# ADC.net
KiCad netlist of a schematic drawn in Altium Designer
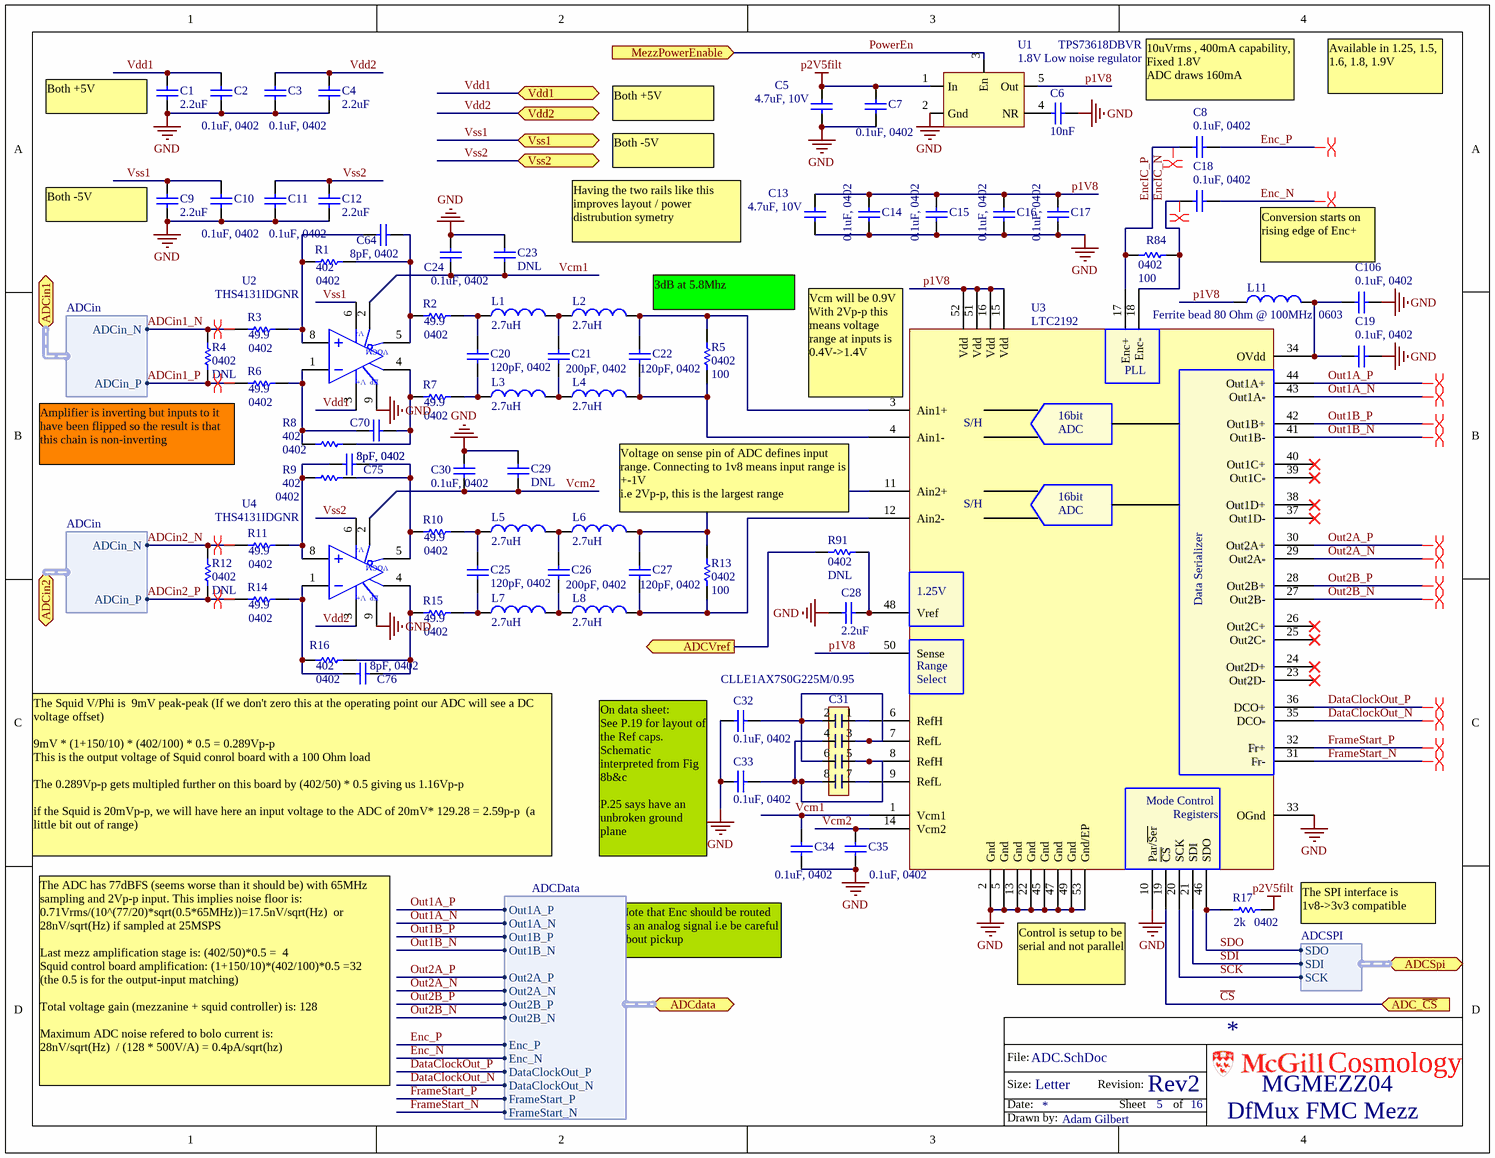
[diagram p0: ADC.SchDoc]

(export (version "E")
  (design (tool "Eeschema 10.0.6"))
  (components
    (comp (ref "C1")
      (value "2.2uF")
      (footprint "0603")
      (description "Capacitor, Ceramic, 0603")
      (fields (field (name "MANUFACTURER") "TDK Corporation"))
      (libsource (lib "MGMEZZ04") (part "CAP 0603"))
    )
    (comp (ref "C2")
      (value "0.1uF, 0402")
      (footprint "0402")
      (description "Capacitor, Ceramic, 0402")
      (fields (field (name "MANUFACTURER") "TDK Corporation"))
      (libsource (lib "MGMEZZ04") (part "CAP 0603"))
    )
    (comp (ref "C3")
      (value "0.1uF, 0402")
      (footprint "0402")
      (description "Capacitor, Ceramic, 0402")
      (fields (field (name "MANUFACTURER") "TDK Corporation"))
      (libsource (lib "MGMEZZ04") (part "CAP 0603"))
    )
    (comp (ref "C4")
      (value "2.2uF")
      (footprint "0603")
      (description "Capacitor, Ceramic, 0603")
      (fields (field (name "MANUFACTURER") "TDK Corporation"))
      (libsource (lib "MGMEZZ04") (part "CAP 0603"))
    )
    (comp (ref "C5")
      (value "4.7uF, 10V")
      (footprint "0805")
      (description "Capacitor, Ceramic, 0805")
      (fields (field (name "MANUFACTURER") "Taiyo Yuden"))
      (libsource (lib "MGMEZZ04") (part "CAP 0805"))
    )
    (comp (ref "C6")
      (value "10nF")
      (footprint "0603")
      (description "Capacitor, Ceramic, 0603")
      (fields (field (name "MANUFACTURER") "Generic"))
      (libsource (lib "MGMEZZ04") (part "CAP 0603"))
    )
    (comp (ref "C7")
      (value "0.1uF, 0402")
      (footprint "0402")
      (description "Capacitor, Ceramic, 0402")
      (fields (field (name "MANUFACTURER") "TDK Corporation"))
      (libsource (lib "MGMEZZ04") (part "CAP 0603"))
    )
    (comp (ref "C8")
      (value "0.1uF, 0402")
      (footprint "0402")
      (description "Capacitor, Ceramic, 0402")
      (fields (field (name "MANUFACTURER") "TDK Corporation"))
      (libsource (lib "MGMEZZ04") (part "CAP 0603"))
    )
    (comp (ref "C9")
      (value "2.2uF")
      (footprint "0603")
      (description "Capacitor, Ceramic, 0603")
      (fields (field (name "MANUFACTURER") "TDK Corporation"))
      (libsource (lib "MGMEZZ04") (part "CAP 0603"))
    )
    (comp (ref "C10")
      (value "0.1uF, 0402")
      (footprint "0402")
      (description "Capacitor, Ceramic, 0402")
      (fields (field (name "MANUFACTURER") "TDK Corporation"))
      (libsource (lib "MGMEZZ04") (part "CAP 0603"))
    )
    (comp (ref "C11")
      (value "0.1uF, 0402")
      (footprint "0402")
      (description "Capacitor, Ceramic, 0402")
      (fields (field (name "MANUFACTURER") "TDK Corporation"))
      (libsource (lib "MGMEZZ04") (part "CAP 0603"))
    )
    (comp (ref "C12")
      (value "2.2uF")
      (footprint "0603")
      (description "Capacitor, Ceramic, 0603")
      (fields (field (name "MANUFACTURER") "TDK Corporation"))
      (libsource (lib "MGMEZZ04") (part "CAP 0603"))
    )
    (comp (ref "C13")
      (value "4.7uF, 10V")
      (footprint "0805")
      (description "Capacitor, Ceramic, 0805")
      (fields (field (name "MANUFACTURER") "Taiyo Yuden"))
      (libsource (lib "MGMEZZ04") (part "CAP 0805"))
    )
    (comp (ref "C14")
      (value "0.1uF, 0402")
      (footprint "0402")
      (description "Capacitor, Ceramic, 0402")
      (fields (field (name "MANUFACTURER") "TDK Corporation"))
      (libsource (lib "MGMEZZ04") (part "CAP 0603"))
    )
    (comp (ref "C15")
      (value "0.1uF, 0402")
      (footprint "0402")
      (description "Capacitor, Ceramic, 0402")
      (fields (field (name "MANUFACTURER") "TDK Corporation"))
      (libsource (lib "MGMEZZ04") (part "CAP 0603"))
    )
    (comp (ref "C16")
      (value "0.1uF, 0402")
      (footprint "0402")
      (description "Capacitor, Ceramic, 0402")
      (fields (field (name "MANUFACTURER") "TDK Corporation"))
      (libsource (lib "MGMEZZ04") (part "CAP 0603"))
    )
    (comp (ref "C17")
      (value "0.1uF, 0402")
      (footprint "0402")
      (description "Capacitor, Ceramic, 0402")
      (fields (field (name "MANUFACTURER") "TDK Corporation"))
      (libsource (lib "MGMEZZ04") (part "CAP 0603"))
    )
    (comp (ref "C18")
      (value "0.1uF, 0402")
      (footprint "0402")
      (description "Capacitor, Ceramic, 0402")
      (fields (field (name "MANUFACTURER") "TDK Corporation"))
      (libsource (lib "MGMEZZ04") (part "CAP 0603"))
    )
    (comp (ref "C19")
      (value "0.1uF, 0402")
      (footprint "0402")
      (description "Capacitor, Ceramic, 0402")
      (fields (field (name "MANUFACTURER") "TDK Corporation"))
      (libsource (lib "MGMEZZ04") (part "CAP 0603"))
    )
    (comp (ref "C20")
      (value "120pF, 0402")
      (footprint "0402")
      (description "Capacitor, Ceramic, 0402")
      (fields (field (name "MANUFACTURER") "Generic"))
      (libsource (lib "MGMEZZ04") (part "CAP 0402"))
    )
    (comp (ref "C21")
      (value "200pF, 0402")
      (footprint "0402")
      (description "Capacitor, Ceramic, 0402")
      (fields (field (name "MANUFACTURER") "Generic"))
      (libsource (lib "MGMEZZ04") (part "CAP 0402"))
    )
    (comp (ref "C22")
      (value "120pF, 0402")
      (footprint "0402")
      (description "Capacitor, Ceramic, 0402")
      (fields (field (name "MANUFACTURER") "Generic"))
      (libsource (lib "MGMEZZ04") (part "CAP 0402"))
    )
    (comp (ref "C23")
      (value "DNL")
      (footprint "0603")
      (description "Capacitor, Ceramic, 0603")
      (fields (field (name "MANUFACTURER") "TDK Corporation"))
      (libsource (lib "MGMEZZ04") (part "CAP 0603"))
    )
    (comp (ref "C24")
      (value "0.1uF, 0402")
      (footprint "0402")
      (description "Capacitor, Ceramic, 0402")
      (fields (field (name "MANUFACTURER") "TDK Corporation"))
      (libsource (lib "MGMEZZ04") (part "CAP 0603"))
    )
    (comp (ref "C25")
      (value "120pF, 0402")
      (footprint "0402")
      (description "Capacitor, Ceramic, 0402")
      (fields (field (name "MANUFACTURER") "Generic"))
      (libsource (lib "MGMEZZ04") (part "CAP 0402"))
    )
    (comp (ref "C26")
      (value "200pF, 0402")
      (footprint "0402")
      (description "Capacitor, Ceramic, 0402")
      (fields (field (name "MANUFACTURER") "Generic"))
      (libsource (lib "MGMEZZ04") (part "CAP 0402"))
    )
    (comp (ref "C27")
      (value "120pF, 0402")
      (footprint "0402")
      (description "Capacitor, Ceramic, 0402")
      (fields (field (name "MANUFACTURER") "Generic"))
      (libsource (lib "MGMEZZ04") (part "CAP 0402"))
    )
    (comp (ref "C28")
      (value "2.2uF")
      (footprint "0603")
      (description "Capacitor, Ceramic, 0603")
      (fields (field (name "MANUFACTURER") "TDK Corporation"))
      (libsource (lib "MGMEZZ04") (part "CAP 0603"))
    )
    (comp (ref "C29")
      (value "DNL")
      (footprint "0603")
      (description "Capacitor, Ceramic, 0603")
      (fields (field (name "MANUFACTURER") "TDK Corporation"))
      (libsource (lib "MGMEZZ04") (part "CAP 0603"))
    )
    (comp (ref "C30")
      (value "0.1uF, 0402")
      (footprint "0402")
      (description "Capacitor, Ceramic, 0402")
      (fields (field (name "MANUFACTURER") "TDK Corporation"))
      (libsource (lib "MGMEZZ04") (part "CAP 0603"))
    )
    (comp (ref "C31")
      (value "CLLE1AX7S0G225M/0.95")
      (footprint "CLLE1")
      (description "2.2uFx4 4V 0805 Cap Array")
      (fields (field (name "MANUFACTURER") "TDK Corporation"))
      (libsource (lib "MGMEZZ04") (part "CapArray0805"))
    )
    (comp (ref "C32")
      (value "0.1uF, 0402")
      (footprint "0402")
      (description "Capacitor, Ceramic, 0402")
      (fields (field (name "MANUFACTURER") "TDK Corporation"))
      (libsource (lib "MGMEZZ04") (part "CAP 0603"))
    )
    (comp (ref "C33")
      (value "0.1uF, 0402")
      (footprint "0402")
      (description "Capacitor, Ceramic, 0402")
      (fields (field (name "MANUFACTURER") "TDK Corporation"))
      (libsource (lib "MGMEZZ04") (part "CAP 0603"))
    )
    (comp (ref "C34")
      (value "0.1uF, 0402")
      (footprint "0402")
      (description "Capacitor, Ceramic, 0402")
      (fields (field (name "MANUFACTURER") "TDK Corporation"))
      (libsource (lib "MGMEZZ04") (part "CAP 0603"))
    )
    (comp (ref "C35")
      (value "0.1uF, 0402")
      (footprint "0402")
      (description "Capacitor, Ceramic, 0402")
      (fields (field (name "MANUFACTURER") "TDK Corporation"))
      (libsource (lib "MGMEZZ04") (part "CAP 0603"))
    )
    (comp (ref "C64")
      (value "8pF, 0402")
      (footprint "0402")
      (description "Capacitor, Ceramic, 0402")
      (fields (field (name "MANUFACTURER") "Generic"))
      (libsource (lib "MGMEZZ04") (part "CAP 0402"))
    )
    (comp (ref "C70")
      (value "8pF, 0402")
      (footprint "0402")
      (description "Capacitor, Ceramic, 0402")
      (fields (field (name "MANUFACTURER") "Generic"))
      (libsource (lib "MGMEZZ04") (part "CAP 0402"))
    )
    (comp (ref "C75")
      (value "8pF, 0402")
      (footprint "0402")
      (description "Capacitor, Ceramic, 0402")
      (fields (field (name "MANUFACTURER") "Generic"))
      (libsource (lib "MGMEZZ04") (part "CAP 0402"))
    )
    (comp (ref "C76")
      (value "8pF, 0402")
      (footprint "0402")
      (description "Capacitor, Ceramic, 0402")
      (fields (field (name "MANUFACTURER") "Generic"))
      (libsource (lib "MGMEZZ04") (part "CAP 0402"))
    )
    (comp (ref "C106")
      (value "0.1uF, 0402")
      (footprint "0402")
      (description "Capacitor, Ceramic, 0402")
      (fields (field (name "MANUFACTURER") "TDK Corporation"))
      (libsource (lib "MGMEZZ04") (part "CAP 0603"))
    )
    (comp (ref "L1")
      (value "2.7uH")
      (footprint "0603")
      (description "Inductor 0603")
      (fields (field (name "MANUFACTURER") "TDK Corporation"))
      (libsource (lib "MGMEZZ04") (part "IND 0603"))
    )
    (comp (ref "L2")
      (value "2.7uH")
      (footprint "0603")
      (description "Inductor 0603")
      (fields (field (name "MANUFACTURER") "TDK Corporation"))
      (libsource (lib "MGMEZZ04") (part "IND 0603"))
    )
    (comp (ref "L3")
      (value "2.7uH")
      (footprint "0603")
      (description "Inductor 0603")
      (fields (field (name "MANUFACTURER") "TDK Corporation"))
      (libsource (lib "MGMEZZ04") (part "IND 0603"))
    )
    (comp (ref "L4")
      (value "2.7uH")
      (footprint "0603")
      (description "Inductor 0603")
      (fields (field (name "MANUFACTURER") "TDK Corporation"))
      (libsource (lib "MGMEZZ04") (part "IND 0603"))
    )
    (comp (ref "L5")
      (value "2.7uH")
      (footprint "0603")
      (description "Inductor 0603")
      (fields (field (name "MANUFACTURER") "TDK Corporation"))
      (libsource (lib "MGMEZZ04") (part "IND 0603"))
    )
    (comp (ref "L6")
      (value "2.7uH")
      (footprint "0603")
      (description "Inductor 0603")
      (fields (field (name "MANUFACTURER") "TDK Corporation"))
      (libsource (lib "MGMEZZ04") (part "IND 0603"))
    )
    (comp (ref "L7")
      (value "2.7uH")
      (footprint "0603")
      (description "Inductor 0603")
      (fields (field (name "MANUFACTURER") "TDK Corporation"))
      (libsource (lib "MGMEZZ04") (part "IND 0603"))
    )
    (comp (ref "L8")
      (value "2.7uH")
      (footprint "0603")
      (description "Inductor 0603")
      (fields (field (name "MANUFACTURER") "TDK Corporation"))
      (libsource (lib "MGMEZZ04") (part "IND 0603"))
    )
    (comp (ref "L11")
      (value "Ferrite bead 80 Ohm @ 100MHz  0603")
      (footprint "0603")
      (description "Inductor 0603")
      (fields (field (name "MANUFACTURER") "Abracon Corporation"))
      (libsource (lib "MGMEZZ04") (part "IND 0603"))
    )
    (comp (ref "R1")
      (value "402")
      (footprint "0402")
      (description "Resistor")
      (fields (field (name "MANUFACTURER") "Generic"))
      (libsource (lib "MGMEZZ04") (part "RES 0402"))
    )
    (comp (ref "R2")
      (value "49.9")
      (footprint "0402")
      (description "Resistor")
      (fields (field (name "MANUFACTURER") "Generic"))
      (libsource (lib "MGMEZZ04") (part "RES 0402"))
    )
    (comp (ref "R3")
      (value "49.9")
      (footprint "0402")
      (description "Resistor")
      (fields (field (name "MANUFACTURER") "Generic"))
      (libsource (lib "MGMEZZ04") (part "RES 0402"))
    )
    (comp (ref "R4")
      (value "DNL")
      (footprint "0402")
      (description "Resistor")
      (fields (field (name "MANUFACTURER") "Generic"))
      (libsource (lib "MGMEZZ04") (part "RES 0402"))
    )
    (comp (ref "R5")
      (value "100")
      (footprint "0402")
      (description "Resistor")
      (fields (field (name "MANUFACTURER") "Generic"))
      (libsource (lib "MGMEZZ04") (part "RES 0402"))
    )
    (comp (ref "R6")
      (value "49.9")
      (footprint "0402")
      (description "Resistor")
      (fields (field (name "MANUFACTURER") "Generic"))
      (libsource (lib "MGMEZZ04") (part "RES 0402"))
    )
    (comp (ref "R7")
      (value "49.9")
      (footprint "0402")
      (description "Resistor")
      (fields (field (name "MANUFACTURER") "Generic"))
      (libsource (lib "MGMEZZ04") (part "RES 0402"))
    )
    (comp (ref "R8")
      (value "402")
      (footprint "0402")
      (description "Resistor")
      (fields (field (name "MANUFACTURER") "Generic"))
      (libsource (lib "MGMEZZ04") (part "RES 0402"))
    )
    (comp (ref "R9")
      (value "402")
      (footprint "0402")
      (description "Resistor")
      (fields (field (name "MANUFACTURER") "Generic"))
      (libsource (lib "MGMEZZ04") (part "RES 0402"))
    )
    (comp (ref "R10")
      (value "49.9")
      (footprint "0402")
      (description "Resistor")
      (fields (field (name "MANUFACTURER") "Generic"))
      (libsource (lib "MGMEZZ04") (part "RES 0402"))
    )
    (comp (ref "R11")
      (value "49.9")
      (footprint "0402")
      (description "Resistor")
      (fields (field (name "MANUFACTURER") "Generic"))
      (libsource (lib "MGMEZZ04") (part "RES 0402"))
    )
    (comp (ref "R12")
      (value "DNL")
      (footprint "0402")
      (description "Resistor")
      (fields (field (name "MANUFACTURER") "Generic"))
      (libsource (lib "MGMEZZ04") (part "RES 0402"))
    )
    (comp (ref "R13")
      (value "100")
      (footprint "0402")
      (description "Resistor")
      (fields (field (name "MANUFACTURER") "Generic"))
      (libsource (lib "MGMEZZ04") (part "RES 0402"))
    )
    (comp (ref "R14")
      (value "49.9")
      (footprint "0402")
      (description "Resistor")
      (fields (field (name "MANUFACTURER") "Generic"))
      (libsource (lib "MGMEZZ04") (part "RES 0402"))
    )
    (comp (ref "R15")
      (value "49.9")
      (footprint "0402")
      (description "Resistor")
      (fields (field (name "MANUFACTURER") "Generic"))
      (libsource (lib "MGMEZZ04") (part "RES 0402"))
    )
    (comp (ref "R16")
      (value "402")
      (footprint "0402")
      (description "Resistor")
      (fields (field (name "MANUFACTURER") "Generic"))
      (libsource (lib "MGMEZZ04") (part "RES 0402"))
    )
    (comp (ref "R17")
      (value "2k")
      (footprint "0402")
      (description "Resistor")
      (fields (field (name "MANUFACTURER") "Generic"))
      (libsource (lib "MGMEZZ04") (part "RES 0402"))
    )
    (comp (ref "R84")
      (value "100")
      (footprint "0402")
      (description "Resistor")
      (fields (field (name "MANUFACTURER") "Generic"))
      (libsource (lib "MGMEZZ04") (part "RES 0402"))
    )
    (comp (ref "R91")
      (value "DNL")
      (footprint "0402")
      (description "Resistor")
      (fields (field (name "MANUFACTURER") "Generic"))
      (libsource (lib "MGMEZZ04") (part "RES 0402"))
    )
    (comp (ref "U1")
      (value "1.8V Low noise regulator")
      (footprint "SOT23-5")
      (description "Fixed 1.8V 10uVrms noise 400mA regulator")
      (fields
        (field (name "MANUFACTURER PART NUMBER 1") "TPS73618DBVR")
        (field (name "MANUFACTURER") "Texas Instruments")
      )
      (libsource (lib "MGMEZZ04") (part "TPS73618DBVR"))
    )
    (comp (ref "U2")
      (value "THS4131IDGNR")
      (footprint "SOP8-EP-127P600-8N")
      (description "IC OPAMP DIFF 225MHZ SGL 8MSOP")
      (fields (field (name "MANUFACTURER") "Texas Instruments"))
      (libsource (lib "MGMEZZ04") (part "THS4131IDGNR"))
    )
    (comp (ref "U3")
      (value "LTC2192")
      (footprint "QFN50P800X700X80_HS-53N")
      (description "IC ADC 16BIT PAR/SRL 65MSP 52QFN")
      (fields (field (name "MANUFACTURER") "Linear Technology"))
      (libsource (lib "MGMEZZ04") (part "LTC2192"))
    )
    (comp (ref "U4")
      (value "THS4131IDGNR")
      (footprint "SOP8-EP-127P600-8N")
      (description "IC OPAMP DIFF 225MHZ SGL 8MSOP")
      (fields (field (name "MANUFACTURER") "Texas Instruments"))
      (libsource (lib "MGMEZZ04") (part "THS4131IDGNR"))
    )
  )
  (nets
    (net (code "4") (name "/ADCVref") (class "Default")
      (node (ref "R91") (pin "2") (pinfunction "2_2") (pintype "passive"))
    )
    (net (code "5") (name "/ADCin1_N") (class "Default")
      (node (ref "R3") (pin "1") (pinfunction "1_1") (pintype "passive"))
      (node (ref "R4") (pin "2") (pinfunction "2_2") (pintype "passive"))
    )
    (net (code "6") (name "/ADCin1_P") (class "Default")
      (node (ref "R4") (pin "1") (pinfunction "1_1") (pintype "passive"))
      (node (ref "R6") (pin "1") (pinfunction "1_1") (pintype "passive"))
    )
    (net (code "7") (name "/ADCin2_N") (class "Default")
      (node (ref "R11") (pin "1") (pinfunction "1_1") (pintype "passive"))
      (node (ref "R12") (pin "2") (pinfunction "2_2") (pintype "passive"))
    )
    (net (code "8") (name "/ADCin2_P") (class "Default")
      (node (ref "R12") (pin "1") (pinfunction "1_1") (pintype "passive"))
      (node (ref "R14") (pin "1") (pinfunction "1_1") (pintype "passive"))
    )
    (net (code "9") (name "/DataClockOut_N") (class "Default")
      (node (ref "U3") (pin "35") (pinfunction "DCO-_35") (pintype "passive"))
    )
    (net (code "10") (name "/DataClockOut_P") (class "Default")
      (node (ref "U3") (pin "36") (pinfunction "DCO+_36") (pintype "passive"))
    )
    (net (code "11") (name "/EncIC_N") (class "Default")
      (node (ref "C18") (pin "1") (pinfunction "1_1") (pintype "passive"))
      (node (ref "R84") (pin "1") (pinfunction "1_1") (pintype "passive"))
      (node (ref "U3") (pin "18") (pinfunction "Enc-_18") (pintype "passive"))
    )
    (net (code "12") (name "/EncIC_P") (class "Default")
      (node (ref "C8") (pin "1") (pinfunction "1_1") (pintype "passive"))
      (node (ref "R84") (pin "2") (pinfunction "2_2") (pintype "passive"))
      (node (ref "U3") (pin "17") (pinfunction "Enc+_17") (pintype "passive"))
    )
    (net (code "13") (name "/Enc_N") (class "Default")
      (node (ref "C18") (pin "2") (pinfunction "2_2") (pintype "passive"))
    )
    (net (code "14") (name "/Enc_P") (class "Default")
      (node (ref "C8") (pin "2") (pinfunction "2_2") (pintype "passive"))
    )
    (net (code "15") (name "/FrameStart_N") (class "Default")
      (node (ref "U3") (pin "31") (pinfunction "Fr-_31") (pintype "passive"))
    )
    (net (code "16") (name "/FrameStart_P") (class "Default")
      (node (ref "U3") (pin "32") (pinfunction "Fr+_32") (pintype "passive"))
    )
    (net (code "17") (name "/Out1A_N") (class "Default")
      (node (ref "U3") (pin "43") (pinfunction "Out1A-_43") (pintype "passive"))
    )
    (net (code "18") (name "/Out1A_P") (class "Default")
      (node (ref "U3") (pin "44") (pinfunction "Out1A+_44") (pintype "passive"))
    )
    (net (code "19") (name "/Out1B_N") (class "Default")
      (node (ref "U3") (pin "41") (pinfunction "Out1B-_41") (pintype "passive"))
    )
    (net (code "20") (name "/Out1B_P") (class "Default")
      (node (ref "U3") (pin "42") (pinfunction "Out1B+_42") (pintype "passive"))
    )
    (net (code "21") (name "/Out2A_N") (class "Default")
      (node (ref "U3") (pin "29") (pinfunction "Out2A-_29") (pintype "passive"))
    )
    (net (code "22") (name "/Out2A_P") (class "Default")
      (node (ref "U3") (pin "30") (pinfunction "Out2A+_30") (pintype "passive"))
    )
    (net (code "23") (name "/Out2B_N") (class "Default")
      (node (ref "U3") (pin "27") (pinfunction "Out2B-_27") (pintype "passive"))
    )
    (net (code "24") (name "/Out2B_P") (class "Default")
      (node (ref "U3") (pin "28") (pinfunction "Out2B+_28") (pintype "passive"))
    )
    (net (code "25") (name "/PowerEn") (class "Default")
      (node (ref "U1") (pin "3") (pinfunction "En_3") (pintype "passive"))
    )
    (net (code "26") (name "/SCK") (class "Default")
      (node (ref "U3") (pin "20") (pinfunction "SCK_20") (pintype "passive"))
    )
    (net (code "27") (name "/SDI") (class "Default")
      (node (ref "U3") (pin "21") (pinfunction "SDI_21") (pintype "passive"))
    )
    (net (code "28") (name "/SDO") (class "Default")
      (node (ref "R17") (pin "2") (pinfunction "2_2") (pintype "passive"))
      (node (ref "U3") (pin "46") (pinfunction "SDO_46") (pintype "passive"))
    )
    (net (code "29") (name "/Vcm1") (class "Default")
      (node (ref "C23") (pin "1") (pinfunction "1_1") (pintype "passive"))
      (node (ref "C24") (pin "2") (pinfunction "2_2") (pintype "passive"))
      (node (ref "C34") (pin "1") (pinfunction "1_1") (pintype "passive"))
      (node (ref "U2") (pin "2") (pinfunction "VOCM_2") (pintype "passive"))
      (node (ref "U3") (pin "1") (pinfunction "Vcm1_1") (pintype "passive"))
    )
    (net (code "30") (name "/Vcm2") (class "Default")
      (node (ref "C29") (pin "1") (pinfunction "1_1") (pintype "passive"))
      (node (ref "C30") (pin "2") (pinfunction "2_2") (pintype "passive"))
      (node (ref "C35") (pin "1") (pinfunction "1_1") (pintype "passive"))
      (node (ref "U3") (pin "14") (pinfunction "Vcm2_14") (pintype "passive"))
      (node (ref "U4") (pin "2") (pinfunction "VOCM_2") (pintype "passive"))
    )
    (net (code "31") (name "/Vdd1") (class "Default")
      (node (ref "C1") (pin "1") (pinfunction "1_1") (pintype "passive"))
      (node (ref "C2") (pin "2") (pinfunction "2_2") (pintype "passive"))
      (node (ref "U2") (pin "3") (pinfunction "V+_3") (pintype "power_in"))
    )
    (net (code "32") (name "/Vdd2") (class "Default")
      (node (ref "C3") (pin "2") (pinfunction "2_2") (pintype "passive"))
      (node (ref "C4") (pin "1") (pinfunction "1_1") (pintype "passive"))
      (node (ref "U4") (pin "3") (pinfunction "V+_3") (pintype "power_in"))
    )
    (net (code "33") (name "/Vss1") (class "Default")
      (node (ref "C10") (pin "2") (pinfunction "2_2") (pintype "passive"))
      (node (ref "C9") (pin "1") (pinfunction "1_1") (pintype "passive"))
      (node (ref "U2") (pin "6") (pinfunction "V-_6") (pintype "power_in"))
    )
    (net (code "34") (name "/Vss2") (class "Default")
      (node (ref "C11") (pin "2") (pinfunction "2_2") (pintype "passive"))
      (node (ref "C12") (pin "1") (pinfunction "1_1") (pintype "passive"))
      (node (ref "U4") (pin "6") (pinfunction "V-_6") (pintype "power_in"))
    )
    (net (code "35") (name "/p1V8") (class "Default")
      (node (ref "C13") (pin "2") (pinfunction "2_2") (pintype "passive"))
      (node (ref "C14") (pin "2") (pinfunction "2_2") (pintype "passive"))
      (node (ref "C15") (pin "2") (pinfunction "2_2") (pintype "passive"))
      (node (ref "C16") (pin "2") (pinfunction "2_2") (pintype "passive"))
      (node (ref "C17") (pin "2") (pinfunction "2_2") (pintype "passive"))
      (node (ref "L11") (pin "1") (pinfunction "1_1") (pintype "passive"))
      (node (ref "U1") (pin "5") (pinfunction "Out_5") (pintype "passive"))
      (node (ref "U3") (pin "15") (pinfunction "Vdd_15") (pintype "passive"))
      (node (ref "U3") (pin "16") (pinfunction "Vdd_16") (pintype "passive"))
      (node (ref "U3") (pin "50") (pinfunction "Sense_50") (pintype "passive"))
      (node (ref "U3") (pin "51") (pinfunction "Vdd_51") (pintype "passive"))
      (node (ref "U3") (pin "52") (pinfunction "Vdd_52") (pintype "passive"))
    )
    (net (code "39") (name "/~{CS}") (class "Default")
      (node (ref "U3") (pin "19") (pinfunction "~{CS}_19") (pintype "passive"))
    )
    (net (code "40") (name "GND") (class "Default")
      (node (ref "C1") (pin "2") (pinfunction "2_2") (pintype "passive"))
      (node (ref "C10") (pin "1") (pinfunction "1_1") (pintype "passive"))
      (node (ref "C106") (pin "2") (pinfunction "2_2") (pintype "passive"))
      (node (ref "C11") (pin "1") (pinfunction "1_1") (pintype "passive"))
      (node (ref "C12") (pin "2") (pinfunction "2_2") (pintype "passive"))
      (node (ref "C13") (pin "1") (pinfunction "1_1") (pintype "passive"))
      (node (ref "C14") (pin "1") (pinfunction "1_1") (pintype "passive"))
      (node (ref "C15") (pin "1") (pinfunction "1_1") (pintype "passive"))
      (node (ref "C16") (pin "1") (pinfunction "1_1") (pintype "passive"))
      (node (ref "C17") (pin "1") (pinfunction "1_1") (pintype "passive"))
      (node (ref "C19") (pin "2") (pinfunction "2_2") (pintype "passive"))
      (node (ref "C2") (pin "1") (pinfunction "1_1") (pintype "passive"))
      (node (ref "C23") (pin "2") (pinfunction "2_2") (pintype "passive"))
      (node (ref "C24") (pin "1") (pinfunction "1_1") (pintype "passive"))
      (node (ref "C28") (pin "2") (pinfunction "2_2") (pintype "passive"))
      (node (ref "C29") (pin "2") (pinfunction "2_2") (pintype "passive"))
      (node (ref "C3") (pin "1") (pinfunction "1_1") (pintype "passive"))
      (node (ref "C30") (pin "1") (pinfunction "1_1") (pintype "passive"))
      (node (ref "C32") (pin "1") (pinfunction "1_1") (pintype "passive"))
      (node (ref "C33") (pin "1") (pinfunction "1_1") (pintype "passive"))
      (node (ref "C34") (pin "2") (pinfunction "2_2") (pintype "passive"))
      (node (ref "C35") (pin "2") (pinfunction "2_2") (pintype "passive"))
      (node (ref "C4") (pin "2") (pinfunction "2_2") (pintype "passive"))
      (node (ref "C5") (pin "1") (pinfunction "1_1") (pintype "passive"))
      (node (ref "C6") (pin "1") (pinfunction "1_1") (pintype "passive"))
      (node (ref "C7") (pin "1") (pinfunction "1_1") (pintype "passive"))
      (node (ref "C9") (pin "2") (pinfunction "2_2") (pintype "passive"))
      (node (ref "U1") (pin "2") (pinfunction "Gnd_2") (pintype "passive"))
      (node (ref "U2") (pin "9") (pinfunction "EP_9") (pintype "power_in"))
      (node (ref "U3") (pin "10") (pinfunction "Par/~{Ser}_10") (pintype "passive"))
      (node (ref "U3") (pin "13") (pinfunction "Gnd_13") (pintype "passive"))
      (node (ref "U3") (pin "2") (pinfunction "Gnd_2") (pintype "passive"))
      (node (ref "U3") (pin "22") (pinfunction "Gnd_22") (pintype "passive"))
      (node (ref "U3") (pin "33") (pinfunction "OGnd_33") (pintype "passive"))
      (node (ref "U3") (pin "45") (pinfunction "Gnd_45") (pintype "passive"))
      (node (ref "U3") (pin "47") (pinfunction "Gnd_47") (pintype "passive"))
      (node (ref "U3") (pin "49") (pinfunction "Gnd_49") (pintype "passive"))
      (node (ref "U3") (pin "5") (pinfunction "Gnd_5") (pintype "passive"))
      (node (ref "U3") (pin "53") (pinfunction "Gnd/EP_53") (pintype "passive"))
      (node (ref "U4") (pin "9") (pinfunction "EP_9") (pintype "power_in"))
    )
    (net (code "41") (name "Net-(C20-Pad1)") (class "Default")
      (node (ref "C20") (pin "1") (pinfunction "1_1") (pintype "passive"))
      (node (ref "L3") (pin "1") (pinfunction "1_1") (pintype "passive"))
      (node (ref "R7") (pin "2") (pinfunction "2_2") (pintype "passive"))
    )
    (net (code "42") (name "Net-(C20-Pad2)") (class "Default")
      (node (ref "C20") (pin "2") (pinfunction "2_2") (pintype "passive"))
      (node (ref "L1") (pin "1") (pinfunction "1_1") (pintype "passive"))
      (node (ref "R2") (pin "2") (pinfunction "2_2") (pintype "passive"))
    )
    (net (code "43") (name "Net-(C21-Pad1)") (class "Default")
      (node (ref "C21") (pin "1") (pinfunction "1_1") (pintype "passive"))
      (node (ref "L3") (pin "2") (pinfunction "2_2") (pintype "passive"))
      (node (ref "L4") (pin "1") (pinfunction "1_1") (pintype "passive"))
    )
    (net (code "44") (name "Net-(C21-Pad2)") (class "Default")
      (node (ref "C21") (pin "2") (pinfunction "2_2") (pintype "passive"))
      (node (ref "L1") (pin "2") (pinfunction "2_2") (pintype "passive"))
      (node (ref "L2") (pin "1") (pinfunction "1_1") (pintype "passive"))
    )
    (net (code "45") (name "Net-(C25-Pad1)") (class "Default")
      (node (ref "C25") (pin "1") (pinfunction "1_1") (pintype "passive"))
      (node (ref "L7") (pin "1") (pinfunction "1_1") (pintype "passive"))
      (node (ref "R15") (pin "2") (pinfunction "2_2") (pintype "passive"))
    )
    (net (code "46") (name "Net-(C25-Pad2)") (class "Default")
      (node (ref "C25") (pin "2") (pinfunction "2_2") (pintype "passive"))
      (node (ref "L5") (pin "1") (pinfunction "1_1") (pintype "passive"))
      (node (ref "R10") (pin "2") (pinfunction "2_2") (pintype "passive"))
    )
    (net (code "47") (name "Net-(C26-Pad1)") (class "Default")
      (node (ref "C26") (pin "1") (pinfunction "1_1") (pintype "passive"))
      (node (ref "L7") (pin "2") (pinfunction "2_2") (pintype "passive"))
      (node (ref "L8") (pin "1") (pinfunction "1_1") (pintype "passive"))
    )
    (net (code "48") (name "Net-(C26-Pad2)") (class "Default")
      (node (ref "C26") (pin "2") (pinfunction "2_2") (pintype "passive"))
      (node (ref "L5") (pin "2") (pinfunction "2_2") (pintype "passive"))
      (node (ref "L6") (pin "1") (pinfunction "1_1") (pintype "passive"))
    )
    (net (code "49") (name "Net-(C31-Pad1)") (class "Default")
      (node (ref "C31") (pin "1") (pinfunction "1_1") (pintype "passive"))
      (node (ref "U3") (pin "6") (pinfunction "RefH_6") (pintype "passive"))
    )
    (net (code "50") (name "Net-(C31-Pad2)") (class "Default")
      (node (ref "C31") (pin "2") (pinfunction "2_2") (pintype "passive"))
      (node (ref "C31") (pin "3") (pinfunction "3_3") (pintype "passive"))
      (node (ref "C31") (pin "6") (pinfunction "6_6") (pintype "passive"))
      (node (ref "C32") (pin "2") (pinfunction "2_2") (pintype "passive"))
      (node (ref "U3") (pin "7") (pinfunction "RefL_7") (pintype "passive"))
    )
    (net (code "51") (name "Net-(C31-Pad4)") (class "Default")
      (node (ref "C31") (pin "4") (pinfunction "4_4") (pintype "passive"))
      (node (ref "C31") (pin "5") (pinfunction "5_5") (pintype "passive"))
      (node (ref "C31") (pin "8") (pinfunction "8_8") (pintype "passive"))
      (node (ref "C33") (pin "2") (pinfunction "2_2") (pintype "passive"))
      (node (ref "U3") (pin "8") (pinfunction "RefH_8") (pintype "passive"))
    )
    (net (code "52") (name "Net-(C31-Pad7)") (class "Default")
      (node (ref "C31") (pin "7") (pinfunction "7_7") (pintype "passive"))
      (node (ref "U3") (pin "9") (pinfunction "RefL_9") (pintype "passive"))
    )
    (net (code "53") (name "Net-(U1-NR)") (class "Default")
      (node (ref "C6") (pin "2") (pinfunction "2_2") (pintype "passive"))
      (node (ref "U1") (pin "4") (pinfunction "NR_4") (pintype "passive"))
    )
    (net (code "54") (name "Net-(U2-IN+)") (class "Default")
      (node (ref "C64") (pin "2") (pinfunction "2_2") (pintype "passive"))
      (node (ref "R1") (pin "1") (pinfunction "1_1") (pintype "passive"))
      (node (ref "R3") (pin "2") (pinfunction "2_2") (pintype "passive"))
      (node (ref "U2") (pin "8") (pinfunction "IN+_8") (pintype "passive"))
    )
    (net (code "55") (name "Net-(U2-IN-)") (class "Default")
      (node (ref "C70") (pin "2") (pinfunction "2_2") (pintype "passive"))
      (node (ref "R6") (pin "2") (pinfunction "2_2") (pintype "passive"))
      (node (ref "R8") (pin "1") (pinfunction "1_1") (pintype "passive"))
      (node (ref "U2") (pin "1") (pinfunction "IN-_1") (pintype "passive"))
    )
    (net (code "56") (name "Net-(U2-OUT+)") (class "Default")
      (node (ref "C70") (pin "1") (pinfunction "1_1") (pintype "passive"))
      (node (ref "R7") (pin "1") (pinfunction "1_1") (pintype "passive"))
      (node (ref "R8") (pin "2") (pinfunction "2_2") (pintype "passive"))
      (node (ref "U2") (pin "4") (pinfunction "OUT+_4") (pintype "passive"))
    )
    (net (code "57") (name "Net-(U2-OUT-)") (class "Default")
      (node (ref "C64") (pin "1") (pinfunction "1_1") (pintype "passive"))
      (node (ref "R1") (pin "2") (pinfunction "2_2") (pintype "passive"))
      (node (ref "R2") (pin "1") (pinfunction "1_1") (pintype "passive"))
      (node (ref "U2") (pin "5") (pinfunction "OUT-_5") (pintype "passive"))
    )
    (net (code "58") (name "Net-(U3-Ain1+)") (class "Default")
      (node (ref "C22") (pin "2") (pinfunction "2_2") (pintype "passive"))
      (node (ref "L2") (pin "2") (pinfunction "2_2") (pintype "passive"))
      (node (ref "R5") (pin "2") (pinfunction "2_2") (pintype "passive"))
      (node (ref "U3") (pin "3") (pinfunction "Ain1+_3") (pintype "passive"))
    )
    (net (code "59") (name "Net-(U3-Ain1-)") (class "Default")
      (node (ref "C22") (pin "1") (pinfunction "1_1") (pintype "passive"))
      (node (ref "L4") (pin "2") (pinfunction "2_2") (pintype "passive"))
      (node (ref "R5") (pin "1") (pinfunction "1_1") (pintype "passive"))
      (node (ref "U3") (pin "4") (pinfunction "Ain1-_4") (pintype "passive"))
    )
    (net (code "60") (name "Net-(U3-Ain2+)") (class "Default")
      (node (ref "C27") (pin "2") (pinfunction "2_2") (pintype "passive"))
      (node (ref "L6") (pin "2") (pinfunction "2_2") (pintype "passive"))
      (node (ref "R13") (pin "2") (pinfunction "2_2") (pintype "passive"))
      (node (ref "U3") (pin "11") (pinfunction "Ain2+_11") (pintype "passive"))
    )
    (net (code "61") (name "Net-(U3-Ain2-)") (class "Default")
      (node (ref "C27") (pin "1") (pinfunction "1_1") (pintype "passive"))
      (node (ref "L8") (pin "2") (pinfunction "2_2") (pintype "passive"))
      (node (ref "R13") (pin "1") (pinfunction "1_1") (pintype "passive"))
      (node (ref "U3") (pin "12") (pinfunction "Ain2-_12") (pintype "passive"))
    )
    (net (code "62") (name "Net-(U3-OVdd)") (class "Default")
      (node (ref "C106") (pin "1") (pinfunction "1_1") (pintype "passive"))
      (node (ref "C19") (pin "1") (pinfunction "1_1") (pintype "passive"))
      (node (ref "L11") (pin "2") (pinfunction "2_2") (pintype "passive"))
      (node (ref "U3") (pin "34") (pinfunction "OVdd_34") (pintype "passive"))
    )
    (net (code "63") (name "Net-(U3-Vref)") (class "Default")
      (node (ref "C28") (pin "1") (pinfunction "1_1") (pintype "passive"))
      (node (ref "R91") (pin "1") (pinfunction "1_1") (pintype "passive"))
      (node (ref "U3") (pin "48") (pinfunction "Vref_48") (pintype "passive"))
    )
    (net (code "64") (name "Net-(U4-IN+)") (class "Default")
      (node (ref "C75") (pin "2") (pinfunction "2_2") (pintype "passive"))
      (node (ref "R11") (pin "2") (pinfunction "2_2") (pintype "passive"))
      (node (ref "R9") (pin "1") (pinfunction "1_1") (pintype "passive"))
      (node (ref "U4") (pin "8") (pinfunction "IN+_8") (pintype "passive"))
    )
    (net (code "65") (name "Net-(U4-IN-)") (class "Default")
      (node (ref "C76") (pin "2") (pinfunction "2_2") (pintype "passive"))
      (node (ref "R14") (pin "2") (pinfunction "2_2") (pintype "passive"))
      (node (ref "R16") (pin "1") (pinfunction "1_1") (pintype "passive"))
      (node (ref "U4") (pin "1") (pinfunction "IN-_1") (pintype "passive"))
    )
    (net (code "66") (name "Net-(U4-OUT+)") (class "Default")
      (node (ref "C76") (pin "1") (pinfunction "1_1") (pintype "passive"))
      (node (ref "R15") (pin "1") (pinfunction "1_1") (pintype "passive"))
      (node (ref "R16") (pin "2") (pinfunction "2_2") (pintype "passive"))
      (node (ref "U4") (pin "4") (pinfunction "OUT+_4") (pintype "passive"))
    )
    (net (code "67") (name "Net-(U4-OUT-)") (class "Default")
      (node (ref "C75") (pin "1") (pinfunction "1_1") (pintype "passive"))
      (node (ref "R10") (pin "1") (pinfunction "1_1") (pintype "passive"))
      (node (ref "R9") (pin "2") (pinfunction "2_2") (pintype "passive"))
      (node (ref "U4") (pin "5") (pinfunction "OUT-_5") (pintype "passive"))
    )
    (net (code "68") (name "p2V5filt") (class "Default")
      (node (ref "C5") (pin "2") (pinfunction "2_2") (pintype "passive"))
      (node (ref "C7") (pin "2") (pinfunction "2_2") (pintype "passive"))
      (node (ref "R17") (pin "1") (pinfunction "1_1") (pintype "passive"))
      (node (ref "U1") (pin "1") (pinfunction "In_1") (pintype "passive"))
    )
    (net (code "69") (name "unconnected-(U2-NC-Pad7)") (class "Default")
      (node (ref "U2") (pin "7") (pinfunction "NC_7") (pintype "passive"))
    )
    (net (code "70") (name "unconnected-(U3-Out1C+-Pad40)") (class "Default")
      (node (ref "U3") (pin "40") (pinfunction "Out1C+_40") (pintype "passive+no_connect"))
    )
    (net (code "71") (name "unconnected-(U3-Out1C--Pad39)") (class "Default")
      (node (ref "U3") (pin "39") (pinfunction "Out1C-_39") (pintype "passive+no_connect"))
    )
    (net (code "72") (name "unconnected-(U3-Out1D+-Pad38)") (class "Default")
      (node (ref "U3") (pin "38") (pinfunction "Out1D+_38") (pintype "passive+no_connect"))
    )
    (net (code "73") (name "unconnected-(U3-Out1D--Pad37)") (class "Default")
      (node (ref "U3") (pin "37") (pinfunction "Out1D-_37") (pintype "passive+no_connect"))
    )
    (net (code "74") (name "unconnected-(U3-Out2C+-Pad26)") (class "Default")
      (node (ref "U3") (pin "26") (pinfunction "Out2C+_26") (pintype "passive+no_connect"))
    )
    (net (code "75") (name "unconnected-(U3-Out2C--Pad25)") (class "Default")
      (node (ref "U3") (pin "25") (pinfunction "Out2C-_25") (pintype "passive+no_connect"))
    )
    (net (code "76") (name "unconnected-(U3-Out2D+-Pad24)") (class "Default")
      (node (ref "U3") (pin "24") (pinfunction "Out2D+_24") (pintype "passive+no_connect"))
    )
    (net (code "77") (name "unconnected-(U3-Out2D--Pad23)") (class "Default")
      (node (ref "U3") (pin "23") (pinfunction "Out2D-_23") (pintype "passive+no_connect"))
    )
    (net (code "78") (name "unconnected-(U4-NC-Pad7)") (class "Default")
      (node (ref "U4") (pin "7") (pinfunction "NC_7") (pintype "passive"))
    )
  )
)
